# main.net
KiCad netlist of a schematic drawn in Altium Designer
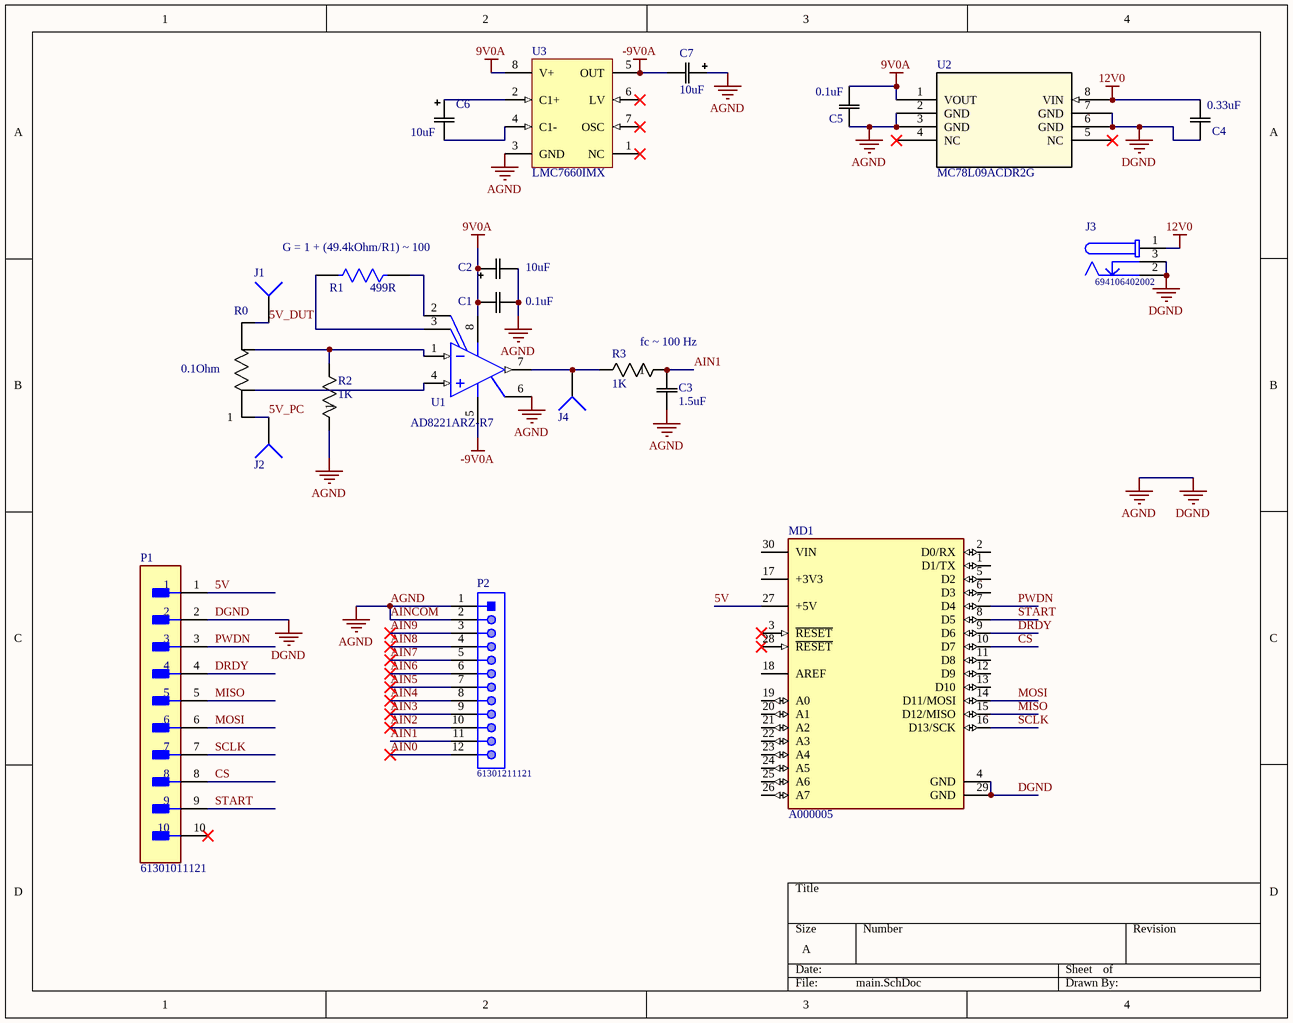
[diagram p0: main.SchDoc]

(export (version "E")
  (design (tool "Eeschema 10.0.6"))
  (components
    (comp (ref "C1")
      (value "0.1uF")
      (footprint "CAP_0603M")
      (description "0.1uF 0603")
      (fields
        (field (name "MANUFACTURER_PART_NUMBER") "0603YC683KAT2A")
        (field (name "COPYRIGHT") "Copyright (C) 2022 Ultra Librarian. All rights reserved.")
      )
      (libsource (lib "M202A") (part "CAP_0603M"))
    )
    (comp (ref "C2")
      (value "10uF")
      (footprint "CAP_1206M")
      (description "No Description Available")
      (fields
        (field (name "MANUFACTURER_PART_NUMBER") "SMC1206K183")
        (field (name "COPYRIGHT") "Copyright (C) 2022 Ultra Librarian. All rights reserved.")
      )
      (libsource (lib "M202A") (part "CAP_1206M"))
    )
    (comp (ref "C3")
      (value "1.5uF")
      (footprint "CAP_0603M")
      (description "1.5uF 0603")
      (fields
        (field (name "MANUFACTURER_PART_NUMBER") "0603YC683KAT2A")
        (field (name "COPYRIGHT") "Copyright (C) 2022 Ultra Librarian. All rights reserved.")
      )
      (libsource (lib "M202A") (part "CAP_0603M"))
    )
    (comp (ref "C4")
      (value "0.33uF")
      (footprint "CAP_0603M")
      (description "0.33uF 0603")
      (fields
        (field (name "MANUFACTURER_PART_NUMBER") "0603YC683KAT2A")
        (field (name "COPYRIGHT") "Copyright (C) 2022 Ultra Librarian. All rights reserved.")
      )
      (libsource (lib "M202A") (part "CAP_0603M"))
    )
    (comp (ref "C5")
      (value "0.1uF")
      (footprint "CAP_0603M")
      (description "0.1uF 0603")
      (fields
        (field (name "MANUFACTURER_PART_NUMBER") "0603YC683KAT2A")
        (field (name "COPYRIGHT") "Copyright (C) 2022 Ultra Librarian. All rights reserved.")
      )
      (libsource (lib "M202A") (part "CAP_0603M"))
    )
    (comp (ref "C6")
      (value "10uF")
      (footprint "CAP_1206M")
      (description "No Description Available")
      (fields
        (field (name "MANUFACTURER_PART_NUMBER") "SMC1206K183")
        (field (name "COPYRIGHT") "Copyright (C) 2022 Ultra Librarian. All rights reserved.")
      )
      (libsource (lib "M202A") (part "CAP_1206M"))
    )
    (comp (ref "C7")
      (value "10uF")
      (footprint "CAP_1206M")
      (description "No Description Available")
      (fields
        (field (name "MANUFACTURER_PART_NUMBER") "SMC1206K183")
        (field (name "COPYRIGHT") "Copyright (C) 2022 Ultra Librarian. All rights reserved.")
      )
      (libsource (lib "M202A") (part "CAP_1206M"))
    )
    (comp (ref "J1")
      (value "Socket")
      (footprint "PIN1")
      (fields (field (name "PUBLISHER") "Altium Limited"))
      (libsource (lib "Miscellaneous Connectors") (part "Socket"))
    )
    (comp (ref "J2")
      (value "Socket")
      (footprint "PIN1")
      (fields (field (name "PUBLISHER") "Altium Limited"))
      (libsource (lib "Miscellaneous Connectors") (part "Socket"))
    )
    (comp (ref "J3")
      (value "694106402002")
      (footprint "694106402002")
      (description "DC Power Jack Connector WR-DC, Male, Vertical, THT, 3 A, 20 V")
      (fields (field (name "MANUFACTURER") "Wurth Elektronik") (field (name "PUBLISHER") "WurthElektronik"))
      (libsource (lib "Altium Content Vault") (part "WE-JACK-2CD3-RN"))
    )
    (comp (ref "J4")
      (value "Socket")
      (footprint "PIN1")
      (fields (field (name "PUBLISHER") "Altium Limited"))
      (libsource (lib "Miscellaneous Connectors") (part "Socket"))
    )
    (comp (ref "MD1")
      (value "A000005")
      (footprint "FP-A000005-MFG")
      (description "ARDUINO NANO ATMEGA328 EVAL BRD")
      (libsource (lib "Altium Content Vault") (part "d190c066e99afd1c6882cf92e11b2cc"))
    )
    (comp (ref "P1")
      (value "61301011121")
      (footprint "FP-61301011121-MFG")
      (description "CONN HEADER VERT 10POS 2.54MM")
      (libsource (lib "Altium Content Vault") (part "aee40dc8b284c03a16094555aa210be"))
    )
    (comp (ref "P2")
      (value "61301211121")
      (footprint "61301211121")
      (description "THT Vertical Pin Header WR-PHD, Pitch 2.54 mm, Single Row, 12 pins")
      (fields (field (name "MANUFACTURER") "Wurth Elektronik") (field (name "PUBLISHER") "WurthElektronik"))
      (libsource (lib "Altium Content Vault") (part "WE-CN-1P-M-R12"))
    )
    (comp (ref "R0")
      (value "0.1Ohm")
      (footprint "Y1487B_VIS")
      (description "PE2512FKE070R1L")
      (fields
        (field (name "MANUFACTURER_PART_NUMBER") "Y14870R01000B9W")
        (field (name "COPYRIGHT") "Copyright (C) 2022 Ultra Librarian. All rights reserved.")
      )
      (libsource (lib "Y14870R01000B9W") (part "Y14870R01000B9W"))
    )
    (comp (ref "R1")
      (value "499R")
      (footprint "FP-RK73H1J-IPC_C")
      (description "499Ω ±0.5% 0.125W Chip Resistor 0603 Flat Chip (Anti-Sulfuration) AEC-Q200 Qualified")
      (fields (field (name "TOLERANCE") "0.5%"))
      (libsource (lib "Altium Content Vault") (part "1029c3af85768c4190bb7ad29bc67b5"))
    )
    (comp (ref "R2")
      (value "1K")
      (footprint "RES_0603")
      (description "1K 0603")
      (fields
        (field (name "MANUFACTURER_PART_NUMBER") "73L2R56J")
        (field (name "COPYRIGHT") "Copyright (C) 2022 Ultra Librarian. All rights reserved.")
      )
      (libsource (lib "M202A") (part "RES_0603M"))
    )
    (comp (ref "R3")
      (value "1K")
      (footprint "RES_0603")
      (description "1K 0603")
      (fields
        (field (name "MANUFACTURER_PART_NUMBER") "73L2R56J")
        (field (name "COPYRIGHT") "Copyright (C) 2022 Ultra Librarian. All rights reserved.")
      )
      (libsource (lib "M202A") (part "RES_0603M"))
    )
    (comp (ref "U1")
      (value "AD8221ARZ-R7")
      (footprint "ADI-R-8_M")
      (fields (field (name "MANUFACTURER") "Analog Devices"))
      (libsource (lib "Altium Content Vault") (part "ADI-AD8221-8"))
    )
    (comp (ref "U2")
      (value "MC78L09ACDR2G")
      (footprint "SOIC8_ONS")
      (description "No Description Available")
      (fields (field (name "COPYRIGHT") "Copyright (C) 2022 Ultra Librarian. All rights reserved."))
      (libsource (lib "M202A") (part "MC78L09ACDR2G"))
    )
    (comp (ref "U3")
      (value "LMC7660IMX")
      (footprint "D0008A_L")
      (description "Switched Capacitor Voltage Converter, 8-pin Narrow SOIC")
      (fields (field (name "MANUFACTURER") "Texas Instruments"))
      (libsource (lib "Altium Content Vault") (part "PM-CHP-LMC7660IM-8"))
    )
  )
  (nets
    (net (code "1") (name "-9V0A") (class "Default")
      (node (ref "C7") (pin "2") (pinfunction "2_2") (pintype "passive"))
      (node (ref "U1") (pin "5") (pinfunction "VS-_5") (pintype "power_in"))
      (node (ref "U3") (pin "5") (pinfunction "OUT_5") (pintype "power_in"))
    )
    (net (code "2") (name "/5V") (class "Default")
      (node (ref "MD1") (pin "27") (pinfunction "+5V_27") (pintype "power_in"))
      (node (ref "P1") (pin "1") (pinfunction "1_1") (pintype "passive"))
    )
    (net (code "3") (name "/5V_DUT") (class "Default")
      (node (ref "J1") (pin "1") (pinfunction "1_1") (pintype "passive"))
      (node (ref "R0") (pin "4") (pinfunction "4_4") (pintype "passive"))
    )
    (net (code "4") (name "/5V_PC") (class "Default")
      (node (ref "J2") (pin "1") (pinfunction "1_1") (pintype "passive"))
      (node (ref "R0") (pin "1") (pinfunction "1_1") (pintype "passive"))
    )
    (net (code "5") (name "/AIN0") (class "Default")
      (node (ref "P2") (pin "12") (pinfunction "12_12") (pintype "passive+no_connect"))
    )
    (net (code "6") (name "/AIN1") (class "Default")
      (node (ref "C3") (pin "2") (pinfunction "12_2") (pintype "passive"))
      (node (ref "P2") (pin "11") (pinfunction "11_11") (pintype "passive"))
      (node (ref "R3") (pin "1") (pinfunction "1_1") (pintype "passive"))
    )
    (net (code "7") (name "/AIN2") (class "Default")
      (node (ref "P2") (pin "10") (pinfunction "10_10") (pintype "passive+no_connect"))
    )
    (net (code "8") (name "/AIN3") (class "Default")
      (node (ref "P2") (pin "9") (pinfunction "9_9") (pintype "passive+no_connect"))
    )
    (net (code "9") (name "/AIN4") (class "Default")
      (node (ref "P2") (pin "8") (pinfunction "8_8") (pintype "passive+no_connect"))
    )
    (net (code "10") (name "/AIN5") (class "Default")
      (node (ref "P2") (pin "7") (pinfunction "7_7") (pintype "passive+no_connect"))
    )
    (net (code "11") (name "/AIN6") (class "Default")
      (node (ref "P2") (pin "6") (pinfunction "6_6") (pintype "passive+no_connect"))
    )
    (net (code "12") (name "/AIN7") (class "Default")
      (node (ref "P2") (pin "5") (pinfunction "5_5") (pintype "passive+no_connect"))
    )
    (net (code "13") (name "/AIN8") (class "Default")
      (node (ref "P2") (pin "4") (pinfunction "4_4") (pintype "passive+no_connect"))
    )
    (net (code "14") (name "/AIN9") (class "Default")
      (node (ref "P2") (pin "3") (pinfunction "3_3") (pintype "passive+no_connect"))
    )
    (net (code "15") (name "/CS") (class "Default")
      (node (ref "MD1") (pin "10") (pinfunction "D7_10") (pintype "bidirectional"))
      (node (ref "P1") (pin "8") (pinfunction "8_8") (pintype "passive"))
    )
    (net (code "16") (name "/DRDY") (class "Default")
      (node (ref "MD1") (pin "9") (pinfunction "D6_9") (pintype "bidirectional"))
      (node (ref "P1") (pin "4") (pinfunction "4_4") (pintype "passive"))
    )
    (net (code "17") (name "/MISO") (class "Default")
      (node (ref "MD1") (pin "15") (pinfunction "D12/MISO_15") (pintype "bidirectional"))
      (node (ref "P1") (pin "5") (pinfunction "5_5") (pintype "passive"))
    )
    (net (code "18") (name "/MOSI") (class "Default")
      (node (ref "MD1") (pin "14") (pinfunction "D11/MOSI_14") (pintype "bidirectional"))
      (node (ref "P1") (pin "6") (pinfunction "6_6") (pintype "passive"))
    )
    (net (code "19") (name "/PWDN") (class "Default")
      (node (ref "MD1") (pin "7") (pinfunction "D4_7") (pintype "bidirectional"))
      (node (ref "P1") (pin "3") (pinfunction "3_3") (pintype "passive"))
    )
    (net (code "20") (name "/SCLK") (class "Default")
      (node (ref "MD1") (pin "16") (pinfunction "D13/SCK_16") (pintype "bidirectional"))
      (node (ref "P1") (pin "7") (pinfunction "7_7") (pintype "passive"))
    )
    (net (code "21") (name "/START") (class "Default")
      (node (ref "MD1") (pin "8") (pinfunction "D5_8") (pintype "bidirectional"))
      (node (ref "P1") (pin "9") (pinfunction "9_9") (pintype "passive"))
    )
    (net (code "22") (name "9V0A") (class "Default")
      (node (ref "C1") (pin "1") (pinfunction "11_1") (pintype "passive"))
      (node (ref "C2") (pin "1") (pinfunction "1_1") (pintype "passive"))
      (node (ref "C5") (pin "2") (pinfunction "12_2") (pintype "passive"))
      (node (ref "U1") (pin "8") (pinfunction "VS+_8") (pintype "power_in"))
      (node (ref "U2") (pin "1") (pinfunction "VOUT_1") (pintype "power_in"))
      (node (ref "U3") (pin "8") (pinfunction "V+_8") (pintype "power_in"))
    )
    (net (code "23") (name "12V0") (class "Default")
      (node (ref "C4") (pin "1") (pinfunction "11_1") (pintype "passive"))
      (node (ref "J3") (pin "1") (pinfunction "1_1") (pintype "passive"))
      (node (ref "U2") (pin "8") (pinfunction "VIN_8") (pintype "input"))
    )
    (net (code "24") (name "AGND") (class "Default")
      (node (ref "C1") (pin "2") (pinfunction "12_2") (pintype "passive"))
      (node (ref "C2") (pin "2") (pinfunction "2_2") (pintype "passive"))
      (node (ref "C3") (pin "1") (pinfunction "11_1") (pintype "passive"))
      (node (ref "C4") (pin "2") (pinfunction "12_2") (pintype "passive"))
      (node (ref "C5") (pin "1") (pinfunction "11_1") (pintype "passive"))
      (node (ref "C7") (pin "1") (pinfunction "1_1") (pintype "passive"))
      (node (ref "J3") (pin "2") (pinfunction "2_2") (pintype "passive"))
      (node (ref "J3") (pin "3") (pinfunction "3_3") (pintype "passive"))
      (node (ref "MD1") (pin "29") (pinfunction "GND_29") (pintype "power_in"))
      (node (ref "MD1") (pin "4") (pinfunction "GND_4") (pintype "power_in"))
      (node (ref "P1") (pin "2") (pinfunction "2_2") (pintype "passive"))
      (node (ref "P2") (pin "1") (pinfunction "1_1") (pintype "passive"))
      (node (ref "P2") (pin "2") (pinfunction "2_2") (pintype "passive"))
      (node (ref "R2") (pin "1") (pinfunction "1_1") (pintype "passive"))
      (node (ref "U1") (pin "6") (pinfunction "REF_6") (pintype "passive"))
      (node (ref "U2") (pin "2") (pinfunction "GND_2") (pintype "power_in"))
      (node (ref "U2") (pin "3") (pinfunction "GND_3") (pintype "power_in"))
      (node (ref "U2") (pin "6") (pinfunction "GND_6") (pintype "power_in"))
      (node (ref "U2") (pin "7") (pinfunction "GND_7") (pintype "power_in"))
      (node (ref "U3") (pin "3") (pinfunction "GND_3") (pintype "power_in"))
    )
    (net (code "25") (name "Net-(R1-Pad1)") (class "Default")
      (node (ref "R1") (pin "1") (pinfunction "1_1") (pintype "passive"))
      (node (ref "U1") (pin "2") (pinfunction "RG_2") (pintype "passive"))
    )
    (net (code "26") (name "Net-(R1-Pad2)") (class "Default")
      (node (ref "R1") (pin "2") (pinfunction "2_2") (pintype "passive"))
      (node (ref "U1") (pin "3") (pinfunction "RG_3") (pintype "passive"))
    )
    (net (code "27") (name "Net-(U1-IN+)") (class "Default")
      (node (ref "R0") (pin "2") (pinfunction "2_2") (pintype "passive"))
      (node (ref "U1") (pin "4") (pinfunction "IN+_4") (pintype "input"))
    )
    (net (code "28") (name "Net-(U1-IN-)") (class "Default")
      (node (ref "R0") (pin "3") (pinfunction "3_3") (pintype "passive"))
      (node (ref "R2") (pin "2") (pinfunction "2_2") (pintype "passive"))
      (node (ref "U1") (pin "1") (pinfunction "IN-_1") (pintype "input"))
    )
    (net (code "29") (name "Net-(U1-VOUT)") (class "Default")
      (node (ref "J4") (pin "1") (pinfunction "1_1") (pintype "passive"))
      (node (ref "R3") (pin "2") (pinfunction "2_2") (pintype "passive"))
      (node (ref "U1") (pin "7") (pinfunction "VOUT_7") (pintype "output"))
    )
    (net (code "30") (name "Net-(U3-C1+)") (class "Default")
      (node (ref "C6") (pin "1") (pinfunction "1_1") (pintype "passive"))
      (node (ref "U3") (pin "2") (pinfunction "C1+_2") (pintype "input"))
    )
    (net (code "31") (name "Net-(U3-C1-)") (class "Default")
      (node (ref "C6") (pin "2") (pinfunction "2_2") (pintype "passive"))
      (node (ref "U3") (pin "4") (pinfunction "C1-_4") (pintype "input"))
    )
    (net (code "32") (name "unconnected-(MD1-+3V3-Pad17)") (class "Default")
      (node (ref "MD1") (pin "17") (pinfunction "+3V3_17") (pintype "power_in"))
    )
    (net (code "33") (name "unconnected-(MD1-A0-Pad19)") (class "Default")
      (node (ref "MD1") (pin "19") (pinfunction "A0_19") (pintype "bidirectional"))
    )
    (net (code "34") (name "unconnected-(MD1-A1-Pad20)") (class "Default")
      (node (ref "MD1") (pin "20") (pinfunction "A1_20") (pintype "bidirectional"))
    )
    (net (code "35") (name "unconnected-(MD1-A2-Pad21)") (class "Default")
      (node (ref "MD1") (pin "21") (pinfunction "A2_21") (pintype "bidirectional"))
    )
    (net (code "36") (name "unconnected-(MD1-A3-Pad22)") (class "Default")
      (node (ref "MD1") (pin "22") (pinfunction "A3_22") (pintype "bidirectional"))
    )
    (net (code "37") (name "unconnected-(MD1-A4-Pad23)") (class "Default")
      (node (ref "MD1") (pin "23") (pinfunction "A4_23") (pintype "bidirectional"))
    )
    (net (code "38") (name "unconnected-(MD1-A5-Pad24)") (class "Default")
      (node (ref "MD1") (pin "24") (pinfunction "A5_24") (pintype "bidirectional"))
    )
    (net (code "39") (name "unconnected-(MD1-A6-Pad25)") (class "Default")
      (node (ref "MD1") (pin "25") (pinfunction "A6_25") (pintype "bidirectional"))
    )
    (net (code "40") (name "unconnected-(MD1-A7-Pad26)") (class "Default")
      (node (ref "MD1") (pin "26") (pinfunction "A7_26") (pintype "bidirectional"))
    )
    (net (code "41") (name "unconnected-(MD1-AREF-Pad18)") (class "Default")
      (node (ref "MD1") (pin "18") (pinfunction "AREF_18") (pintype "passive"))
    )
    (net (code "42") (name "unconnected-(MD1-D0{slash}RX-Pad2)") (class "Default")
      (node (ref "MD1") (pin "2") (pinfunction "D0/RX_2") (pintype "bidirectional"))
    )
    (net (code "43") (name "unconnected-(MD1-D1{slash}TX-Pad1)") (class "Default")
      (node (ref "MD1") (pin "1") (pinfunction "D1/TX_1") (pintype "bidirectional"))
    )
    (net (code "44") (name "unconnected-(MD1-D2-Pad5)") (class "Default")
      (node (ref "MD1") (pin "5") (pinfunction "D2_5") (pintype "bidirectional"))
    )
    (net (code "45") (name "unconnected-(MD1-D3-Pad6)") (class "Default")
      (node (ref "MD1") (pin "6") (pinfunction "D3_6") (pintype "bidirectional"))
    )
    (net (code "46") (name "unconnected-(MD1-D8-Pad11)") (class "Default")
      (node (ref "MD1") (pin "11") (pinfunction "D8_11") (pintype "bidirectional"))
    )
    (net (code "47") (name "unconnected-(MD1-D9-Pad12)") (class "Default")
      (node (ref "MD1") (pin "12") (pinfunction "D9_12") (pintype "bidirectional"))
    )
    (net (code "48") (name "unconnected-(MD1-D10-Pad13)") (class "Default")
      (node (ref "MD1") (pin "13") (pinfunction "D10_13") (pintype "bidirectional"))
    )
    (net (code "49") (name "unconnected-(MD1-VIN-Pad30)") (class "Default")
      (node (ref "MD1") (pin "30") (pinfunction "VIN_30") (pintype "power_in"))
    )
    (net (code "50") (name "unconnected-(MD1-~{RESET}-Pad3)") (class "Default")
      (node (ref "MD1") (pin "3") (pinfunction "~{RESET}_3") (pintype "input+no_connect"))
    )
    (net (code "51") (name "unconnected-(MD1-~{RESET}-Pad28)") (class "Default")
      (node (ref "MD1") (pin "28") (pinfunction "~{RESET}_28") (pintype "input+no_connect"))
    )
    (net (code "52") (name "unconnected-(P1-Pad10)") (class "Default")
      (node (ref "P1") (pin "10") (pinfunction "10_10") (pintype "passive+no_connect"))
    )
    (net (code "53") (name "unconnected-(U2-NC-Pad4)") (class "Default")
      (node (ref "U2") (pin "4") (pinfunction "NC_4") (pintype "passive+no_connect"))
    )
    (net (code "54") (name "unconnected-(U2-NC-Pad5)") (class "Default")
      (node (ref "U2") (pin "5") (pinfunction "NC_5") (pintype "passive+no_connect"))
    )
    (net (code "55") (name "unconnected-(U3-LV-Pad6)") (class "Default")
      (node (ref "U3") (pin "6") (pinfunction "LV_6") (pintype "input+no_connect"))
    )
    (net (code "56") (name "unconnected-(U3-NC-Pad1)") (class "Default")
      (node (ref "U3") (pin "1") (pinfunction "NC_1") (pintype "passive+no_connect"))
    )
    (net (code "57") (name "unconnected-(U3-OSC-Pad7)") (class "Default")
      (node (ref "U3") (pin "7") (pinfunction "OSC_7") (pintype "input+no_connect"))
    )
  )
)
